# Bodenfeuchte_RFduino.net
KiCad netlist of a schematic drawn in EAGLE
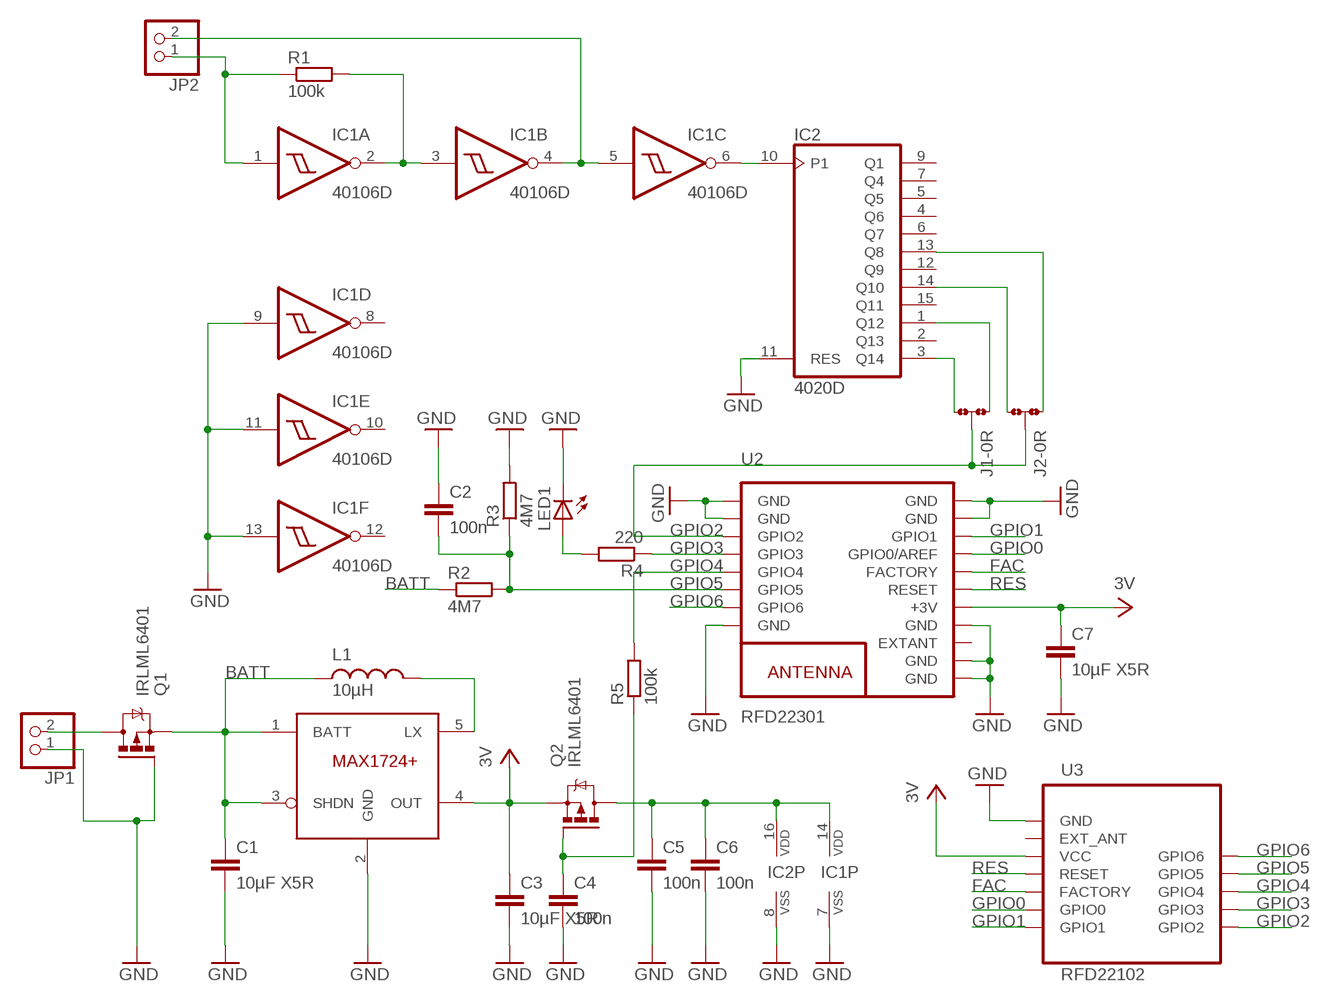
[diagram p0: schematic, sheet 1]

(export (version "E")
  (design (tool "Eeschema 10.0.6"))
  (components
    (comp (ref "C1")
      (value "10µF X5R")
      (footprint "eagle-import:C0805")
      (libsource (lib "eagle-import") (part "C-EUC0805"))
    )
    (comp (ref "C2")
      (value "100n")
      (footprint "eagle-import:C0805")
      (libsource (lib "eagle-import") (part "C-EUC0805"))
    )
    (comp (ref "C3")
      (value "10µF X5R")
      (footprint "eagle-import:C0805")
      (libsource (lib "eagle-import") (part "C-EUC0805"))
    )
    (comp (ref "C4")
      (value "100n")
      (footprint "eagle-import:C0805")
      (libsource (lib "eagle-import") (part "C-EUC0805"))
    )
    (comp (ref "C5")
      (value "100n")
      (footprint "eagle-import:C0805")
      (libsource (lib "eagle-import") (part "C-EUC0805"))
    )
    (comp (ref "C6")
      (value "100n")
      (footprint "eagle-import:C0805")
      (libsource (lib "eagle-import") (part "C-EUC0805"))
    )
    (comp (ref "C7")
      (value "10µF X5R")
      (footprint "eagle-import:C0805")
      (libsource (lib "eagle-import") (part "C-EUC0805"))
    )
    (comp (ref "IC1")
      (value "40106D")
      (footprint "eagle-import:SO14")
      (libsource (lib "eagle-import") (part "40106D"))
    )
    (comp (ref "IC2")
      (value "4020D")
      (footprint "eagle-import:SO16")
      (libsource (lib "eagle-import") (part "4020D"))
    )
    (comp (ref "J1")
      (value "0R-JUMPA")
      (footprint "eagle-import:A0R-JMP")
      (libsource (lib "eagle-import") (part "0R-JUMPA"))
    )
    (comp (ref "J2")
      (value "0R-JUMPA")
      (footprint "eagle-import:A0R-JMP")
      (libsource (lib "eagle-import") (part "0R-JUMPA"))
    )
    (comp (ref "JP1")
      (value "PINHD-1X2")
      (footprint "eagle-import:1X02")
      (libsource (lib "eagle-import") (part "PINHD-1X2"))
    )
    (comp (ref "JP2")
      (value "PINHD-1X2")
      (footprint "eagle-import:1X02")
      (libsource (lib "eagle-import") (part "PINHD-1X2"))
    )
    (comp (ref "L1")
      (value "10µH")
      (footprint "eagle-import:DS1608")
      (libsource (lib "eagle-import") (part "DS1608C"))
    )
    (comp (ref "LED1")
      (value "LEDCHIPLED_1206")
      (footprint "eagle-import:CHIPLED_1206")
      (libsource (lib "eagle-import") (part "LEDCHIPLED_1206"))
    )
    (comp (ref "Q1")
      (value "IRLML6401")
      (footprint "eagle-import:MICRO3")
      (libsource (lib "eagle-import") (part "IRLML5203"))
    )
    (comp (ref "Q2")
      (value "IRLML6401")
      (footprint "eagle-import:MICRO3")
      (libsource (lib "eagle-import") (part "IRLML5203"))
    )
    (comp (ref "R1")
      (value "100k")
      (footprint "eagle-import:R0805")
      (libsource (lib "eagle-import") (part "R-EU_R0805"))
    )
    (comp (ref "R2")
      (value "4M7")
      (footprint "eagle-import:R0805")
      (libsource (lib "eagle-import") (part "R-EU_R0805"))
    )
    (comp (ref "R3")
      (value "4M7")
      (footprint "eagle-import:R0805")
      (libsource (lib "eagle-import") (part "R-EU_R0805"))
    )
    (comp (ref "R4")
      (value "220")
      (footprint "eagle-import:R0805")
      (libsource (lib "eagle-import") (part "R-EU_R0805"))
    )
    (comp (ref "R5")
      (value "100k")
      (footprint "eagle-import:R0805")
      (libsource (lib "eagle-import") (part "R-EU_R0805"))
    )
    (comp (ref "U1")
      (value "MAX1724")
      (footprint "eagle-import:SOT23-5L")
      (libsource (lib "eagle-import") (part "MAX1724"))
    )
    (comp (ref "U2")
      (value "RFD22301")
      (footprint "eagle-import:RFD22301")
      (libsource (lib "eagle-import") (part "RFD22301"))
    )
    (comp (ref "U3")
      (value "RFD22102")
      (footprint "eagle-import:RFD22102")
      (libsource (lib "eagle-import") (part "RFD22102"))
    )
  )
  (nets
    (net (code "1") (name "/BATT") (class "Default")
      (node (ref "C1") (pin "1") (pinfunction "1_1") (pintype "passive"))
      (node (ref "L1") (pin "P$2") (pinfunction "P$2_P$2") (pintype "passive"))
      (node (ref "Q1") (pin "2") (pinfunction "S_2") (pintype "passive"))
      (node (ref "R2") (pin "1") (pinfunction "1_1") (pintype "passive"))
      (node (ref "U1") (pin "1") (pinfunction "BATT_1") (pintype "power_in"))
      (node (ref "U1") (pin "3") (pinfunction "SHDN_3") (pintype "bidirectional"))
    )
    (net (code "2") (name "/FAC") (class "Default")
      (node (ref "U2") (pin "15") (pinfunction "FACTORY_15") (pintype "bidirectional"))
      (node (ref "U3") (pin "FACTORY") (pinfunction "FACTORY_FACTORY") (pintype "bidirectional"))
    )
    (net (code "3") (name "/GPIO0") (class "Default")
      (node (ref "U2") (pin "16") (pinfunction "GPIO0/AREF_16") (pintype "bidirectional"))
      (node (ref "U3") (pin "GPIO0") (pinfunction "GPIO0_GPIO0") (pintype "bidirectional"))
    )
    (net (code "4") (name "/GPIO1") (class "Default")
      (node (ref "U2") (pin "17") (pinfunction "GPIO1_17") (pintype "bidirectional"))
      (node (ref "U3") (pin "GPIO1") (pinfunction "GPIO1_GPIO1") (pintype "bidirectional"))
    )
    (net (code "5") (name "/GPIO2") (class "Default")
      (node (ref "J1") (pin "2") (pinfunction "2_2") (pintype "passive"))
      (node (ref "J2") (pin "2") (pinfunction "2_2") (pintype "passive"))
      (node (ref "U2") (pin "3") (pinfunction "GPIO2_3") (pintype "bidirectional"))
      (node (ref "U3") (pin "GPIO2") (pinfunction "GPIO2_GPIO2") (pintype "bidirectional"))
    )
    (net (code "6") (name "/GPIO3") (class "Default")
      (node (ref "R4") (pin "1") (pinfunction "1_1") (pintype "passive"))
      (node (ref "U2") (pin "4") (pinfunction "GPIO3_4") (pintype "bidirectional"))
      (node (ref "U3") (pin "GPIO3") (pinfunction "GPIO3_GPIO3") (pintype "bidirectional"))
    )
    (net (code "7") (name "/GPIO4") (class "Default")
      (node (ref "R5") (pin "2") (pinfunction "2_2") (pintype "passive"))
      (node (ref "U2") (pin "5") (pinfunction "GPIO4_5") (pintype "bidirectional"))
      (node (ref "U3") (pin "GPIO4") (pinfunction "GPIO4_GPIO4") (pintype "bidirectional"))
    )
    (net (code "8") (name "/GPIO5") (class "Default")
      (node (ref "C2") (pin "2") (pinfunction "2_2") (pintype "passive"))
      (node (ref "R2") (pin "2") (pinfunction "2_2") (pintype "passive"))
      (node (ref "R3") (pin "1") (pinfunction "1_1") (pintype "passive"))
      (node (ref "U2") (pin "6") (pinfunction "GPIO5_6") (pintype "bidirectional"))
      (node (ref "U3") (pin "GPIO5") (pinfunction "GPIO5_GPIO5") (pintype "bidirectional"))
    )
    (net (code "9") (name "/GPIO6") (class "Default")
      (node (ref "U2") (pin "7") (pinfunction "GPIO6_7") (pintype "bidirectional"))
      (node (ref "U3") (pin "GPIO6") (pinfunction "GPIO6_GPIO6") (pintype "bidirectional"))
    )
    (net (code "10") (name "/RES") (class "Default")
      (node (ref "U2") (pin "14") (pinfunction "RESET_14") (pintype "bidirectional"))
      (node (ref "U3") (pin "RESET") (pinfunction "RESET_RESET") (pintype "bidirectional"))
    )
    (net (code "11") (name "3V") (class "Default")
      (node (ref "C3") (pin "1") (pinfunction "1_1") (pintype "passive"))
      (node (ref "C7") (pin "1") (pinfunction "1_1") (pintype "passive"))
      (node (ref "Q2") (pin "2") (pinfunction "S_2") (pintype "passive"))
      (node (ref "U1") (pin "4") (pinfunction "OUT_4") (pintype "output"))
      (node (ref "U2") (pin "13") (pinfunction "+3V_13") (pintype "power_in"))
      (node (ref "U3") (pin "VCC") (pinfunction "VCC_VCC") (pintype "power_in"))
    )
    (net (code "12") (name "GND") (class "Default")
      (node (ref "C1") (pin "2") (pinfunction "2_2") (pintype "passive"))
      (node (ref "C2") (pin "1") (pinfunction "1_1") (pintype "passive"))
      (node (ref "C3") (pin "2") (pinfunction "2_2") (pintype "passive"))
      (node (ref "C4") (pin "2") (pinfunction "2_2") (pintype "passive"))
      (node (ref "C5") (pin "2") (pinfunction "2_2") (pintype "passive"))
      (node (ref "C6") (pin "2") (pinfunction "2_2") (pintype "passive"))
      (node (ref "C7") (pin "2") (pinfunction "2_2") (pintype "passive"))
      (node (ref "IC1") (pin "11") (pinfunction "I_11") (pintype "input"))
      (node (ref "IC1") (pin "13") (pinfunction "I_13") (pintype "input"))
      (node (ref "IC1") (pin "7") (pinfunction "VSS_7") (pintype "power_in"))
      (node (ref "IC1") (pin "9") (pinfunction "I_9") (pintype "input"))
      (node (ref "IC2") (pin "11") (pinfunction "RES_11") (pintype "input"))
      (node (ref "IC2") (pin "8") (pinfunction "VSS_8") (pintype "power_in"))
      (node (ref "JP1") (pin "1") (pinfunction "1_1") (pintype "passive"))
      (node (ref "LED1") (pin "C") (pinfunction "C_C") (pintype "passive"))
      (node (ref "Q1") (pin "1") (pinfunction "G_1") (pintype "passive"))
      (node (ref "R3") (pin "2") (pinfunction "2_2") (pintype "passive"))
      (node (ref "U1") (pin "2") (pinfunction "GND_2") (pintype "power_in"))
      (node (ref "U2") (pin "1") (pinfunction "GND_1") (pintype "power_in"))
      (node (ref "U2") (pin "10") (pinfunction "GND_10") (pintype "power_in"))
      (node (ref "U2") (pin "12") (pinfunction "GND_12") (pintype "power_in"))
      (node (ref "U2") (pin "18") (pinfunction "GND_18") (pintype "power_in"))
      (node (ref "U2") (pin "19") (pinfunction "GND_19") (pintype "power_in"))
      (node (ref "U2") (pin "2") (pinfunction "GND_2") (pintype "power_in"))
      (node (ref "U2") (pin "8") (pinfunction "GND_8") (pintype "power_in"))
      (node (ref "U2") (pin "9") (pinfunction "GND_9") (pintype "power_in"))
      (node (ref "U3") (pin "GND") (pinfunction "GND_GND") (pintype "power_in"))
    )
    (net (code "13") (name "Net-(IC1A-I)") (class "Default")
      (node (ref "IC1") (pin "1") (pinfunction "I_1") (pintype "input"))
      (node (ref "JP2") (pin "1") (pinfunction "1_1") (pintype "passive"))
      (node (ref "R1") (pin "1") (pinfunction "1_1") (pintype "passive"))
    )
    (net (code "14") (name "Net-(IC1A-O)") (class "Default")
      (node (ref "IC1") (pin "2") (pinfunction "O_2") (pintype "output"))
      (node (ref "IC1") (pin "3") (pinfunction "I_3") (pintype "input"))
      (node (ref "R1") (pin "2") (pinfunction "2_2") (pintype "passive"))
    )
    (net (code "15") (name "Net-(IC1B-O)") (class "Default")
      (node (ref "IC1") (pin "4") (pinfunction "O_4") (pintype "output"))
      (node (ref "IC1") (pin "5") (pinfunction "I_5") (pintype "input"))
      (node (ref "JP2") (pin "2") (pinfunction "2_2") (pintype "passive"))
    )
    (net (code "16") (name "Net-(IC1C-O)") (class "Default")
      (node (ref "IC1") (pin "6") (pinfunction "O_6") (pintype "output"))
      (node (ref "IC2") (pin "10") (pinfunction "P1_10") (pintype "input"))
    )
    (net (code "17") (name "Net-(IC1G-VDD)") (class "Default")
      (node (ref "C5") (pin "1") (pinfunction "1_1") (pintype "passive"))
      (node (ref "C6") (pin "1") (pinfunction "1_1") (pintype "passive"))
      (node (ref "IC1") (pin "14") (pinfunction "VDD_14") (pintype "power_in"))
      (node (ref "IC2") (pin "16") (pinfunction "VDD_16") (pintype "power_in"))
      (node (ref "Q2") (pin "3") (pinfunction "D_3") (pintype "passive"))
    )
    (net (code "18") (name "Net-(IC2A-Q8)") (class "Default")
      (node (ref "IC2") (pin "13") (pinfunction "Q8_13") (pintype "output"))
      (node (ref "J2") (pin "1") (pinfunction "1_1") (pintype "passive"))
    )
    (net (code "19") (name "Net-(IC2A-Q10)") (class "Default")
      (node (ref "IC2") (pin "14") (pinfunction "Q10_14") (pintype "output"))
      (node (ref "J2") (pin "3") (pinfunction "3_3") (pintype "passive"))
    )
    (net (code "20") (name "Net-(IC2A-Q12)") (class "Default")
      (node (ref "IC2") (pin "1") (pinfunction "Q12_1") (pintype "output"))
      (node (ref "J1") (pin "1") (pinfunction "1_1") (pintype "passive"))
    )
    (net (code "21") (name "Net-(IC2A-Q14)") (class "Default")
      (node (ref "IC2") (pin "3") (pinfunction "Q14_3") (pintype "output"))
      (node (ref "J1") (pin "3") (pinfunction "3_3") (pintype "passive"))
    )
    (net (code "22") (name "Net-(LED1-PadA)") (class "Default")
      (node (ref "LED1") (pin "A") (pinfunction "A_A") (pintype "passive"))
      (node (ref "R4") (pin "2") (pinfunction "2_2") (pintype "passive"))
    )
    (net (code "23") (name "Net-(Q1-D)") (class "Default")
      (node (ref "JP1") (pin "2") (pinfunction "2_2") (pintype "passive"))
      (node (ref "Q1") (pin "3") (pinfunction "D_3") (pintype "passive"))
    )
    (net (code "24") (name "Net-(Q2-G)") (class "Default")
      (node (ref "C4") (pin "1") (pinfunction "1_1") (pintype "passive"))
      (node (ref "Q2") (pin "1") (pinfunction "G_1") (pintype "passive"))
      (node (ref "R5") (pin "1") (pinfunction "1_1") (pintype "passive"))
    )
    (net (code "25") (name "Net-(U1-LX)") (class "Default")
      (node (ref "L1") (pin "P$1") (pinfunction "P$1_P$1") (pintype "passive"))
      (node (ref "U1") (pin "5") (pinfunction "LX_5") (pintype "input"))
    )
    (net (code "26") (name "unconnected-(IC1D-O-Pad8)") (class "Default")
      (node (ref "IC1") (pin "8") (pinfunction "O_8") (pintype "output"))
    )
    (net (code "27") (name "unconnected-(IC1E-O-Pad10)") (class "Default")
      (node (ref "IC1") (pin "10") (pinfunction "O_10") (pintype "output"))
    )
    (net (code "28") (name "unconnected-(IC1F-O-Pad12)") (class "Default")
      (node (ref "IC1") (pin "12") (pinfunction "O_12") (pintype "output"))
    )
    (net (code "29") (name "unconnected-(IC2A-Q1-Pad9)") (class "Default")
      (node (ref "IC2") (pin "9") (pinfunction "Q1_9") (pintype "output"))
    )
    (net (code "30") (name "unconnected-(IC2A-Q4-Pad7)") (class "Default")
      (node (ref "IC2") (pin "7") (pinfunction "Q4_7") (pintype "output"))
    )
    (net (code "31") (name "unconnected-(IC2A-Q5-Pad5)") (class "Default")
      (node (ref "IC2") (pin "5") (pinfunction "Q5_5") (pintype "output"))
    )
    (net (code "32") (name "unconnected-(IC2A-Q6-Pad4)") (class "Default")
      (node (ref "IC2") (pin "4") (pinfunction "Q6_4") (pintype "output"))
    )
    (net (code "33") (name "unconnected-(IC2A-Q7-Pad6)") (class "Default")
      (node (ref "IC2") (pin "6") (pinfunction "Q7_6") (pintype "output"))
    )
    (net (code "34") (name "unconnected-(IC2A-Q9-Pad12)") (class "Default")
      (node (ref "IC2") (pin "12") (pinfunction "Q9_12") (pintype "output"))
    )
    (net (code "35") (name "unconnected-(IC2A-Q11-Pad15)") (class "Default")
      (node (ref "IC2") (pin "15") (pinfunction "Q11_15") (pintype "output"))
    )
    (net (code "36") (name "unconnected-(IC2A-Q13-Pad2)") (class "Default")
      (node (ref "IC2") (pin "2") (pinfunction "Q13_2") (pintype "output"))
    )
    (net (code "37") (name "unconnected-(U2-EXTANT-Pad11)") (class "Default")
      (node (ref "U2") (pin "11") (pinfunction "EXTANT_11") (pintype "no_connect"))
    )
    (net (code "38") (name "unconnected-(U3-PadEXT_ANT)") (class "Default")
      (node (ref "U3") (pin "EXT_ANT") (pinfunction "EXT_ANT_EXT_ANT") (pintype "no_connect"))
    )
  )
)
